# LevelShifter.net
KiCad netlist of a schematic drawn in Altium Designer
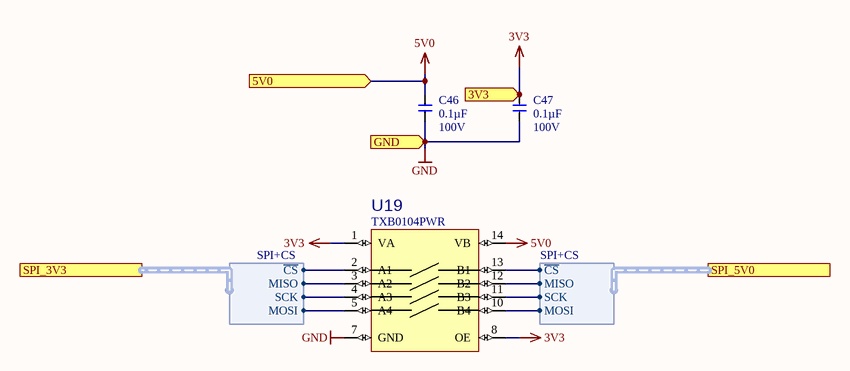
[diagram p0: LevelShifter.SchDoc]

(export (version "E")
  (design (tool "Eeschema 10.0.6"))
  (components
    (comp (ref "C46")
      (value "CAP_CER_100NF_100V")
      (footprint "C0603")
      (description "CAP CER 0.1UF 100V X7S 0603")
      (fields
        (field (name "MANUFACTURER") "TDK Corporation")
        (field (name "TOLERANCE") "±10%")
        (field (name "VOLTAGE - RATED") "100V")
        (field (name "CAPACITANCE") "0.1µF")
      )
      (libsource (lib "Stanford Student Space Initiative") (part "Symbol"))
    )
    (comp (ref "C47")
      (value "CAP_CER_100NF_100V")
      (footprint "C0603")
      (description "CAP CER 0.1UF 100V X7S 0603")
      (fields
        (field (name "MANUFACTURER") "TDK Corporation")
        (field (name "TOLERANCE") "±10%")
        (field (name "VOLTAGE - RATED") "100V")
        (field (name "CAPACITANCE") "0.1µF")
      )
      (libsource (lib "Stanford Student Space Initiative") (part "Symbol"))
    )
    (comp (ref "U19")
      (value "LVLSHFT_TXB0104PWR")
      (footprint "14TSSOP65")
      (description "4 Pin Bidirectional levelshifter 5v-3.3v")
      (fields
        (field (name "MANUFACTURER") "Texas Instruments")
        (field (name "MANUFACTURER PART NUMBER") "TXB0104PWR")
      )
      (libsource (lib "Stanford Student Space Initiative") (part "LVLSHFT_TXB0104PWR"))
    )
  )
  (nets
    (net (code "3") (name "3V3") (class "Default")
      (node (ref "C47") (pin "1") (pintype "passive"))
      (node (ref "U19") (pin "1") (pinfunction "VA_1") (pintype "bidirectional"))
      (node (ref "U19") (pin "8") (pinfunction "OE_8") (pintype "bidirectional"))
    )
    (net (code "4") (name "5V0") (class "Default")
      (node (ref "C46") (pin "1") (pintype "passive"))
      (node (ref "U19") (pin "14") (pinfunction "VB_14") (pintype "bidirectional"))
    )
    (net (code "5") (name "GND") (class "Default")
      (node (ref "C46") (pin "2") (pintype "passive"))
      (node (ref "C47") (pin "2") (pintype "passive"))
      (node (ref "U19") (pin "7") (pinfunction "GND_7") (pintype "bidirectional"))
    )
    (net (code "6") (name "unconnected-(U19-A1-Pad2)") (class "Default")
      (node (ref "U19") (pin "2") (pinfunction "A1_2") (pintype "bidirectional"))
    )
    (net (code "7") (name "unconnected-(U19-A2-Pad3)") (class "Default")
      (node (ref "U19") (pin "3") (pinfunction "A2_3") (pintype "bidirectional"))
    )
    (net (code "8") (name "unconnected-(U19-A3-Pad4)") (class "Default")
      (node (ref "U19") (pin "4") (pinfunction "A3_4") (pintype "bidirectional"))
    )
    (net (code "9") (name "unconnected-(U19-A4-Pad5)") (class "Default")
      (node (ref "U19") (pin "5") (pinfunction "A4_5") (pintype "bidirectional"))
    )
    (net (code "10") (name "unconnected-(U19-B1-Pad13)") (class "Default")
      (node (ref "U19") (pin "13") (pinfunction "B1_13") (pintype "bidirectional"))
    )
    (net (code "11") (name "unconnected-(U19-B2-Pad12)") (class "Default")
      (node (ref "U19") (pin "12") (pinfunction "B2_12") (pintype "bidirectional"))
    )
    (net (code "12") (name "unconnected-(U19-B3-Pad11)") (class "Default")
      (node (ref "U19") (pin "11") (pinfunction "B3_11") (pintype "bidirectional"))
    )
    (net (code "13") (name "unconnected-(U19-B4-Pad10)") (class "Default")
      (node (ref "U19") (pin "10") (pinfunction "B4_10") (pintype "bidirectional"))
    )
  )
)
